# axiom_beta_plugin_module_1xHDMI_v0_8_r1_.net
KiCad netlist of a schematic drawn in EAGLE
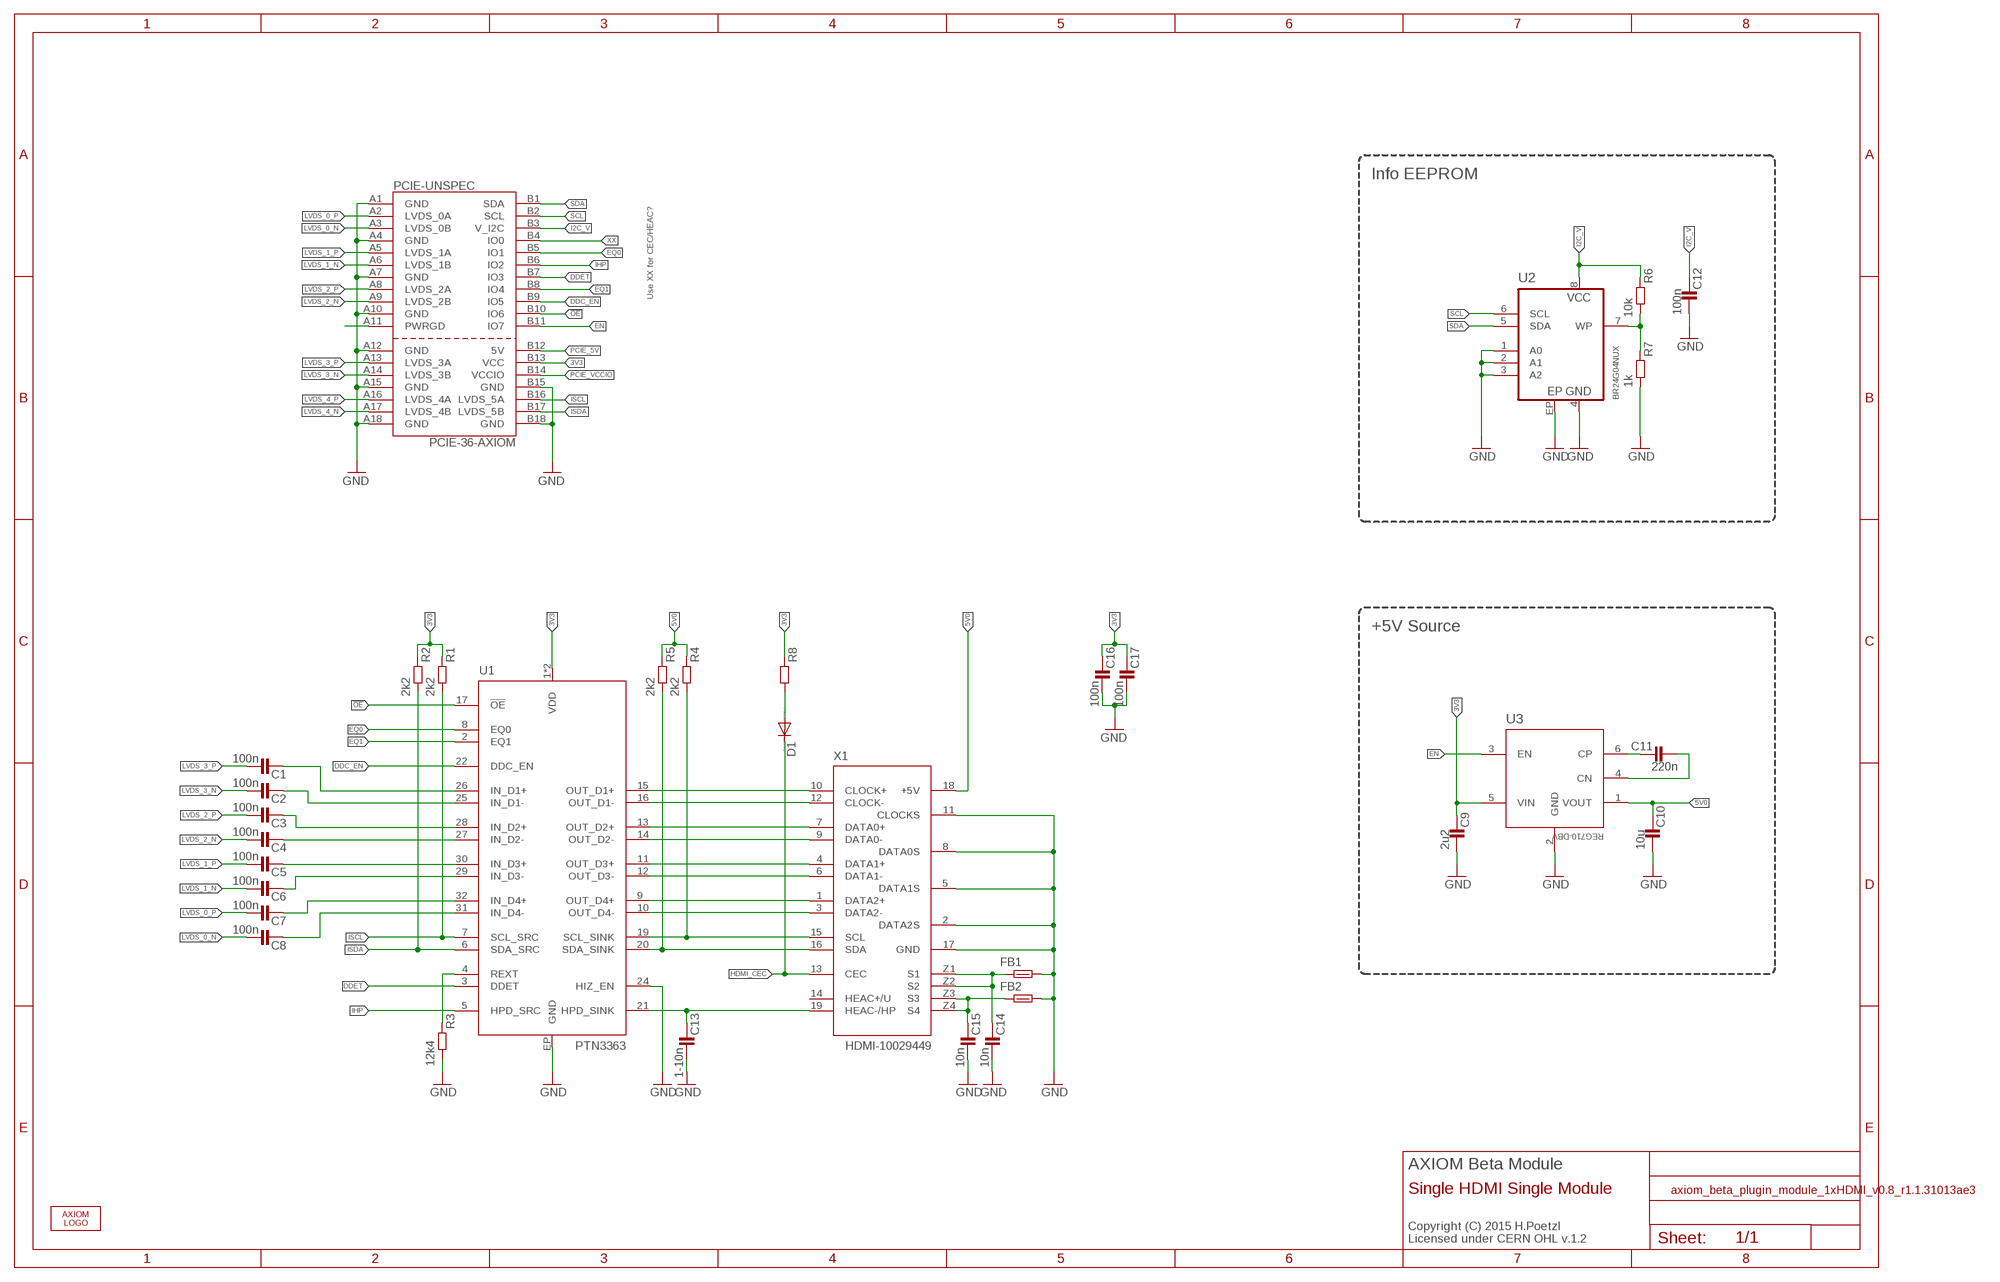
[diagram p0: schematic, sheet 1]

(export (version "E")
  (design (tool "Eeschema 10.0.6"))
  (components
    (comp (ref "C1")
      (value "100n")
      (footprint "eagle-import:0402-C")
      (libsource (lib "eagle-import") (part "C0402-C"))
    )
    (comp (ref "C2")
      (value "100n")
      (footprint "eagle-import:0402-C")
      (libsource (lib "eagle-import") (part "C0402-C"))
    )
    (comp (ref "C3")
      (value "100n")
      (footprint "eagle-import:0402-C")
      (libsource (lib "eagle-import") (part "C0402-C"))
    )
    (comp (ref "C4")
      (value "100n")
      (footprint "eagle-import:0402-C")
      (libsource (lib "eagle-import") (part "C0402-C"))
    )
    (comp (ref "C5")
      (value "100n")
      (footprint "eagle-import:0402-C")
      (libsource (lib "eagle-import") (part "C0402-C"))
    )
    (comp (ref "C6")
      (value "100n")
      (footprint "eagle-import:0402-C")
      (libsource (lib "eagle-import") (part "C0402-C"))
    )
    (comp (ref "C7")
      (value "100n")
      (footprint "eagle-import:0402-C")
      (libsource (lib "eagle-import") (part "C0402-C"))
    )
    (comp (ref "C8")
      (value "100n")
      (footprint "eagle-import:0402-C")
      (libsource (lib "eagle-import") (part "C0402-C"))
    )
    (comp (ref "C9")
      (value "2u2")
      (footprint "eagle-import:0603-B")
      (libsource (lib "eagle-import") (part "C0603-B"))
    )
    (comp (ref "C10")
      (value "10u")
      (footprint "eagle-import:0603-B")
      (libsource (lib "eagle-import") (part "C0603-B"))
    )
    (comp (ref "C11")
      (value "220n")
      (footprint "eagle-import:0603-B")
      (libsource (lib "eagle-import") (part "C0603-B"))
    )
    (comp (ref "C12")
      (value "100n")
      (footprint "eagle-import:0402-B")
      (libsource (lib "eagle-import") (part "C0402-B"))
    )
    (comp (ref "C13")
      (value "1-10n")
      (footprint "eagle-import:0402-B")
      (libsource (lib "eagle-import") (part "C0402-B"))
    )
    (comp (ref "C14")
      (value "10n")
      (footprint "eagle-import:0402-B")
      (libsource (lib "eagle-import") (part "C0402-B"))
    )
    (comp (ref "C15")
      (value "10n")
      (footprint "eagle-import:0402-B")
      (libsource (lib "eagle-import") (part "C0402-B"))
    )
    (comp (ref "C16")
      (value "100n")
      (footprint "eagle-import:0402-B")
      (libsource (lib "eagle-import") (part "C0402-B"))
    )
    (comp (ref "C17")
      (value "100n")
      (footprint "eagle-import:0402-B")
      (libsource (lib "eagle-import") (part "C0402-B"))
    )
    (comp (ref "D1")
      (value "DIODE-SOD523")
      (footprint "eagle-import:SOD523")
      (libsource (lib "eagle-import") (part "DIODE-SOD523"))
    )
    (comp (ref "FB1")
      (value "FB0603-B")
      (footprint "eagle-import:0603-B")
      (libsource (lib "eagle-import") (part "FB0603-B"))
    )
    (comp (ref "FB2")
      (value "FB0603-B")
      (footprint "eagle-import:0603-B")
      (libsource (lib "eagle-import") (part "FB0603-B"))
    )
    (comp (ref "PCIE-UNSPEC")
      (value "PCIE-36-AXIOM")
      (footprint "eagle-import:PCIE-36-AXIOM")
      (libsource (lib "eagle-import") (part "PCIE-36-AXIOM"))
    )
    (comp (ref "R1")
      (value "2k2")
      (footprint "eagle-import:0402-B")
      (libsource (lib "eagle-import") (part "R0402-B"))
    )
    (comp (ref "R2")
      (value "2k2")
      (footprint "eagle-import:0402-B")
      (libsource (lib "eagle-import") (part "R0402-B"))
    )
    (comp (ref "R3")
      (value "12k4")
      (footprint "eagle-import:0402-B")
      (libsource (lib "eagle-import") (part "R0402-B"))
    )
    (comp (ref "R4")
      (value "2k2")
      (footprint "eagle-import:0402-B")
      (libsource (lib "eagle-import") (part "R0402-B"))
    )
    (comp (ref "R5")
      (value "2k2")
      (footprint "eagle-import:0402-B")
      (libsource (lib "eagle-import") (part "R0402-B"))
    )
    (comp (ref "R6")
      (value "10k")
      (footprint "eagle-import:0402-B")
      (libsource (lib "eagle-import") (part "R0402-B"))
    )
    (comp (ref "R7")
      (value "1k")
      (footprint "eagle-import:0402-B")
      (libsource (lib "eagle-import") (part "R0402-B"))
    )
    (comp (ref "R8")
      (value "R0402-B")
      (footprint "eagle-import:0402-B")
      (libsource (lib "eagle-import") (part "R0402-B"))
    )
    (comp (ref "U$1")
      (value "AXIOM_LOGO459X70")
      (footprint "eagle-import:AXIOM_LOGO_459X70")
      (libsource (lib "eagle-import") (part "AXIOM_LOGO459X70"))
    )
    (comp (ref "U1")
      (value "PTN3363")
      (footprint "eagle-import:HVQFN32")
      (libsource (lib "eagle-import") (part "PTN3363"))
    )
    (comp (ref "U2")
      (value "BR24G04NUX")
      (footprint "eagle-import:DFN200X300X100-9N")
      (libsource (lib "eagle-import") (part "BR24G04NUX"))
    )
    (comp (ref "U3")
      (value "REG710-DBV")
      (footprint "eagle-import:DBV")
      (libsource (lib "eagle-import") (part "REG710-DBV"))
    )
    (comp (ref "X1")
      (value "HDMI-10029449")
      (footprint "eagle-import:10029449-X01XLF")
      (libsource (lib "eagle-import") (part "HDMI-10029449"))
    )
  )
  (nets
    (net (code "1") (name "/~{OE}") (class "Default")
      (node (ref "PCIE-UNSPEC") (pin "B10") (pinfunction "IO6_B10") (pintype "passive"))
      (node (ref "U1") (pin "17") (pinfunction "~{OE}_17") (pintype "bidirectional"))
    )
    (net (code "2") (name "3V3") (class "Default")
      (node (ref "C16") (pin "1") (pinfunction "1_1") (pintype "passive"))
      (node (ref "C17") (pin "1") (pinfunction "1_1") (pintype "passive"))
      (node (ref "C9") (pin "1") (pinfunction "1_1") (pintype "passive"))
      (node (ref "PCIE-UNSPEC") (pin "B13") (pinfunction "VCC_B13") (pintype "passive"))
      (node (ref "R1") (pin "1") (pinfunction "1_1") (pintype "passive"))
      (node (ref "R2") (pin "1") (pinfunction "1_1") (pintype "passive"))
      (node (ref "R8") (pin "1") (pinfunction "1_1") (pintype "passive"))
      (node (ref "U1") (pin "1") (pinfunction "VDD_1") (pintype "power_in"))
      (node (ref "U1") (pin "18") (pinfunction "VDD_18") (pintype "power_in"))
      (node (ref "U3") (pin "5") (pinfunction "VIN_5") (pintype "power_in"))
    )
    (net (code "3") (name "5V0") (class "Default")
      (node (ref "C10") (pin "1") (pinfunction "1_1") (pintype "passive"))
      (node (ref "R4") (pin "1") (pinfunction "1_1") (pintype "passive"))
      (node (ref "R5") (pin "1") (pinfunction "1_1") (pintype "passive"))
      (node (ref "U3") (pin "1") (pinfunction "VOUT_1") (pintype "output"))
      (node (ref "X1") (pin "18") (pinfunction "+5V_18") (pintype "power_in"))
    )
    (net (code "4") (name "DDC_EN") (class "Default")
      (node (ref "PCIE-UNSPEC") (pin "B9") (pinfunction "IO5_B9") (pintype "passive"))
      (node (ref "U1") (pin "22") (pinfunction "DDC_EN_22") (pintype "bidirectional"))
    )
    (net (code "5") (name "DDET") (class "Default")
      (node (ref "PCIE-UNSPEC") (pin "B7") (pinfunction "IO3_B7") (pintype "passive"))
      (node (ref "U1") (pin "3") (pinfunction "DDET_3") (pintype "bidirectional"))
    )
    (net (code "6") (name "EN") (class "Default")
      (node (ref "PCIE-UNSPEC") (pin "B11") (pinfunction "IO7_B11") (pintype "passive"))
      (node (ref "U3") (pin "3") (pinfunction "EN_3") (pintype "input"))
    )
    (net (code "7") (name "EQ0") (class "Default")
      (node (ref "PCIE-UNSPEC") (pin "B5") (pinfunction "IO1_B5") (pintype "passive"))
      (node (ref "U1") (pin "8") (pinfunction "EQ0_8") (pintype "bidirectional"))
    )
    (net (code "8") (name "EQ1") (class "Default")
      (node (ref "PCIE-UNSPEC") (pin "B8") (pinfunction "IO4_B8") (pintype "passive"))
      (node (ref "U1") (pin "2") (pinfunction "EQ1_2") (pintype "bidirectional"))
    )
    (net (code "9") (name "GND") (class "Default")
      (node (ref "C10") (pin "2") (pinfunction "2_2") (pintype "passive"))
      (node (ref "C12") (pin "2") (pinfunction "2_2") (pintype "passive"))
      (node (ref "C13") (pin "2") (pinfunction "2_2") (pintype "passive"))
      (node (ref "C14") (pin "2") (pinfunction "2_2") (pintype "passive"))
      (node (ref "C15") (pin "2") (pinfunction "2_2") (pintype "passive"))
      (node (ref "C16") (pin "2") (pinfunction "2_2") (pintype "passive"))
      (node (ref "C17") (pin "2") (pinfunction "2_2") (pintype "passive"))
      (node (ref "C9") (pin "2") (pinfunction "2_2") (pintype "passive"))
      (node (ref "FB1") (pin "2") (pinfunction "2_2") (pintype "passive"))
      (node (ref "FB2") (pin "2") (pinfunction "2_2") (pintype "passive"))
      (node (ref "PCIE-UNSPEC") (pin "A1") (pinfunction "GND_A1") (pintype "passive"))
      (node (ref "PCIE-UNSPEC") (pin "A10") (pinfunction "GND_A10") (pintype "passive"))
      (node (ref "PCIE-UNSPEC") (pin "A12") (pinfunction "GND_A12") (pintype "passive"))
      (node (ref "PCIE-UNSPEC") (pin "A15") (pinfunction "GND_A15") (pintype "passive"))
      (node (ref "PCIE-UNSPEC") (pin "A18") (pinfunction "GND_A18") (pintype "passive"))
      (node (ref "PCIE-UNSPEC") (pin "A4") (pinfunction "GND_A4") (pintype "passive"))
      (node (ref "PCIE-UNSPEC") (pin "A7") (pinfunction "GND_A7") (pintype "passive"))
      (node (ref "PCIE-UNSPEC") (pin "B15") (pinfunction "GND_B15") (pintype "passive"))
      (node (ref "PCIE-UNSPEC") (pin "B18") (pinfunction "GND_B18") (pintype "passive"))
      (node (ref "R3") (pin "2") (pinfunction "2_2") (pintype "passive"))
      (node (ref "R7") (pin "2") (pinfunction "2_2") (pintype "passive"))
      (node (ref "U1") (pin "24") (pinfunction "HIZ_EN_24") (pintype "bidirectional"))
      (node (ref "U1") (pin "EP") (pinfunction "GND_EP") (pintype "bidirectional"))
      (node (ref "U2") (pin "1") (pinfunction "A0_1") (pintype "input"))
      (node (ref "U2") (pin "2") (pinfunction "A1_2") (pintype "input"))
      (node (ref "U2") (pin "3") (pinfunction "A2_3") (pintype "input"))
      (node (ref "U2") (pin "4") (pinfunction "GND_4") (pintype "passive"))
      (node (ref "U2") (pin "EP") (pinfunction "EP_EP") (pintype "passive"))
      (node (ref "U3") (pin "2") (pinfunction "GND_2") (pintype "passive"))
      (node (ref "X1") (pin "11") (pinfunction "CLOCKS_11") (pintype "power_in"))
      (node (ref "X1") (pin "17") (pinfunction "GND_17") (pintype "bidirectional"))
      (node (ref "X1") (pin "2") (pinfunction "DATA2S_2") (pintype "power_in"))
      (node (ref "X1") (pin "5") (pinfunction "DATA1S_5") (pintype "power_in"))
      (node (ref "X1") (pin "8") (pinfunction "DATA0S_8") (pintype "power_in"))
    )
    (net (code "10") (name "HDMI_CEC") (class "Default")
      (node (ref "D1") (pin "C") (pinfunction "C_C") (pintype "passive"))
      (node (ref "X1") (pin "13") (pinfunction "CEC_13") (pintype "bidirectional"))
    )
    (net (code "11") (name "I2C_V") (class "Default")
      (node (ref "C12") (pin "1") (pinfunction "1_1") (pintype "passive"))
      (node (ref "PCIE-UNSPEC") (pin "B3") (pinfunction "V_I2C_B3") (pintype "passive"))
      (node (ref "R6") (pin "1") (pinfunction "1_1") (pintype "passive"))
      (node (ref "U2") (pin "8") (pinfunction "VCC_8") (pintype "power_in"))
    )
    (net (code "12") (name "IHP") (class "Default")
      (node (ref "PCIE-UNSPEC") (pin "B6") (pinfunction "IO2_B6") (pintype "passive"))
      (node (ref "U1") (pin "5") (pinfunction "HPD_SRC_5") (pintype "bidirectional"))
    )
    (net (code "13") (name "ISCL") (class "Default")
      (node (ref "PCIE-UNSPEC") (pin "B16") (pinfunction "LVDS_5A_B16") (pintype "passive"))
      (node (ref "R1") (pin "2") (pinfunction "2_2") (pintype "passive"))
      (node (ref "U1") (pin "7") (pinfunction "SCL_SRC_7") (pintype "bidirectional"))
    )
    (net (code "14") (name "ISDA") (class "Default")
      (node (ref "PCIE-UNSPEC") (pin "B17") (pinfunction "LVDS_5B_B17") (pintype "passive"))
      (node (ref "R2") (pin "2") (pinfunction "2_2") (pintype "passive"))
      (node (ref "U1") (pin "6") (pinfunction "SDA_SRC_6") (pintype "bidirectional"))
    )
    (net (code "15") (name "LVDS_0_N") (class "Default")
      (node (ref "C8") (pin "2") (pinfunction "2_2") (pintype "passive"))
      (node (ref "PCIE-UNSPEC") (pin "A3") (pinfunction "LVDS_0B_A3") (pintype "passive"))
    )
    (net (code "16") (name "LVDS_0_P") (class "Default")
      (node (ref "C7") (pin "2") (pinfunction "2_2") (pintype "passive"))
      (node (ref "PCIE-UNSPEC") (pin "A2") (pinfunction "LVDS_0A_A2") (pintype "passive"))
    )
    (net (code "17") (name "LVDS_1_N") (class "Default")
      (node (ref "C6") (pin "2") (pinfunction "2_2") (pintype "passive"))
      (node (ref "PCIE-UNSPEC") (pin "A6") (pinfunction "LVDS_1B_A6") (pintype "passive"))
    )
    (net (code "18") (name "LVDS_1_P") (class "Default")
      (node (ref "C5") (pin "2") (pinfunction "2_2") (pintype "passive"))
      (node (ref "PCIE-UNSPEC") (pin "A5") (pinfunction "LVDS_1A_A5") (pintype "passive"))
    )
    (net (code "19") (name "LVDS_2_N") (class "Default")
      (node (ref "C4") (pin "2") (pinfunction "2_2") (pintype "passive"))
      (node (ref "PCIE-UNSPEC") (pin "A9") (pinfunction "LVDS_2B_A9") (pintype "passive"))
    )
    (net (code "20") (name "LVDS_2_P") (class "Default")
      (node (ref "C3") (pin "2") (pinfunction "2_2") (pintype "passive"))
      (node (ref "PCIE-UNSPEC") (pin "A8") (pinfunction "LVDS_2A_A8") (pintype "passive"))
    )
    (net (code "21") (name "LVDS_3_N") (class "Default")
      (node (ref "C2") (pin "2") (pinfunction "2_2") (pintype "passive"))
      (node (ref "PCIE-UNSPEC") (pin "A14") (pinfunction "LVDS_3B_A14") (pintype "passive"))
    )
    (net (code "22") (name "LVDS_3_P") (class "Default")
      (node (ref "C1") (pin "2") (pinfunction "2_2") (pintype "passive"))
      (node (ref "PCIE-UNSPEC") (pin "A13") (pinfunction "LVDS_3A_A13") (pintype "passive"))
    )
    (net (code "23") (name "LVDS_4_N") (class "Default")
      (node (ref "PCIE-UNSPEC") (pin "A17") (pinfunction "LVDS_4B_A17") (pintype "passive"))
    )
    (net (code "24") (name "LVDS_4_P") (class "Default")
      (node (ref "PCIE-UNSPEC") (pin "A16") (pinfunction "LVDS_4A_A16") (pintype "passive"))
    )
    (net (code "25") (name "Net-(D1-PadA)") (class "Default")
      (node (ref "D1") (pin "A") (pinfunction "A_A") (pintype "passive"))
      (node (ref "R8") (pin "2") (pinfunction "2_2") (pintype "passive"))
    )
    (net (code "26") (name "Net-(U1-HPD_SINK)") (class "Default")
      (node (ref "C13") (pin "1") (pinfunction "1_1") (pintype "passive"))
      (node (ref "U1") (pin "21") (pinfunction "HPD_SINK_21") (pintype "bidirectional"))
      (node (ref "X1") (pin "19") (pinfunction "HEAC-/HP_19") (pintype "bidirectional"))
    )
    (net (code "27") (name "Net-(U1-IN_D1+)") (class "Default")
      (node (ref "C1") (pin "1") (pinfunction "1_1") (pintype "passive"))
      (node (ref "U1") (pin "26") (pinfunction "IN_D1+_26") (pintype "bidirectional"))
    )
    (net (code "28") (name "Net-(U1-IN_D1-)") (class "Default")
      (node (ref "C2") (pin "1") (pinfunction "1_1") (pintype "passive"))
      (node (ref "U1") (pin "25") (pinfunction "IN_D1-_25") (pintype "bidirectional"))
    )
    (net (code "29") (name "Net-(U1-IN_D2+)") (class "Default")
      (node (ref "C3") (pin "1") (pinfunction "1_1") (pintype "passive"))
      (node (ref "U1") (pin "28") (pinfunction "IN_D2+_28") (pintype "bidirectional"))
    )
    (net (code "30") (name "Net-(U1-IN_D2-)") (class "Default")
      (node (ref "C4") (pin "1") (pinfunction "1_1") (pintype "passive"))
      (node (ref "U1") (pin "27") (pinfunction "IN_D2-_27") (pintype "bidirectional"))
    )
    (net (code "31") (name "Net-(U1-IN_D3+)") (class "Default")
      (node (ref "C5") (pin "1") (pinfunction "1_1") (pintype "passive"))
      (node (ref "U1") (pin "30") (pinfunction "IN_D3+_30") (pintype "bidirectional"))
    )
    (net (code "32") (name "Net-(U1-IN_D3-)") (class "Default")
      (node (ref "C6") (pin "1") (pinfunction "1_1") (pintype "passive"))
      (node (ref "U1") (pin "29") (pinfunction "IN_D3-_29") (pintype "bidirectional"))
    )
    (net (code "33") (name "Net-(U1-IN_D4+)") (class "Default")
      (node (ref "C7") (pin "1") (pinfunction "1_1") (pintype "passive"))
      (node (ref "U1") (pin "32") (pinfunction "IN_D4+_32") (pintype "bidirectional"))
    )
    (net (code "34") (name "Net-(U1-IN_D4-)") (class "Default")
      (node (ref "C8") (pin "1") (pinfunction "1_1") (pintype "passive"))
      (node (ref "U1") (pin "31") (pinfunction "IN_D4-_31") (pintype "bidirectional"))
    )
    (net (code "35") (name "Net-(U1-OUT_D1+)") (class "Default")
      (node (ref "U1") (pin "15") (pinfunction "OUT_D1+_15") (pintype "bidirectional"))
      (node (ref "X1") (pin "10") (pinfunction "CLOCK+_10") (pintype "bidirectional"))
    )
    (net (code "36") (name "Net-(U1-OUT_D1-)") (class "Default")
      (node (ref "U1") (pin "16") (pinfunction "OUT_D1-_16") (pintype "bidirectional"))
      (node (ref "X1") (pin "12") (pinfunction "CLOCK-_12") (pintype "bidirectional"))
    )
    (net (code "37") (name "Net-(U1-OUT_D2+)") (class "Default")
      (node (ref "U1") (pin "13") (pinfunction "OUT_D2+_13") (pintype "bidirectional"))
      (node (ref "X1") (pin "7") (pinfunction "DATA0+_7") (pintype "bidirectional"))
    )
    (net (code "38") (name "Net-(U1-OUT_D2-)") (class "Default")
      (node (ref "U1") (pin "14") (pinfunction "OUT_D2-_14") (pintype "bidirectional"))
      (node (ref "X1") (pin "9") (pinfunction "DATA0-_9") (pintype "bidirectional"))
    )
    (net (code "39") (name "Net-(U1-OUT_D3+)") (class "Default")
      (node (ref "U1") (pin "11") (pinfunction "OUT_D3+_11") (pintype "bidirectional"))
      (node (ref "X1") (pin "4") (pinfunction "DATA1+_4") (pintype "bidirectional"))
    )
    (net (code "40") (name "Net-(U1-OUT_D3-)") (class "Default")
      (node (ref "U1") (pin "12") (pinfunction "OUT_D3-_12") (pintype "bidirectional"))
      (node (ref "X1") (pin "6") (pinfunction "DATA1-_6") (pintype "bidirectional"))
    )
    (net (code "41") (name "Net-(U1-OUT_D4+)") (class "Default")
      (node (ref "U1") (pin "9") (pinfunction "OUT_D4+_9") (pintype "bidirectional"))
      (node (ref "X1") (pin "1") (pinfunction "DATA2+_1") (pintype "bidirectional"))
    )
    (net (code "42") (name "Net-(U1-OUT_D4-)") (class "Default")
      (node (ref "U1") (pin "10") (pinfunction "OUT_D4-_10") (pintype "bidirectional"))
      (node (ref "X1") (pin "3") (pinfunction "DATA2-_3") (pintype "bidirectional"))
    )
    (net (code "43") (name "Net-(U1-REXT)") (class "Default")
      (node (ref "R3") (pin "1") (pinfunction "1_1") (pintype "passive"))
      (node (ref "U1") (pin "4") (pinfunction "REXT_4") (pintype "bidirectional"))
    )
    (net (code "44") (name "Net-(U1-SCL_SINK)") (class "Default")
      (node (ref "R4") (pin "2") (pinfunction "2_2") (pintype "passive"))
      (node (ref "U1") (pin "19") (pinfunction "SCL_SINK_19") (pintype "bidirectional"))
      (node (ref "X1") (pin "15") (pinfunction "SCL_15") (pintype "bidirectional"))
    )
    (net (code "45") (name "Net-(U1-SDA_SINK)") (class "Default")
      (node (ref "R5") (pin "2") (pinfunction "2_2") (pintype "passive"))
      (node (ref "U1") (pin "20") (pinfunction "SDA_SINK_20") (pintype "bidirectional"))
      (node (ref "X1") (pin "16") (pinfunction "SDA_16") (pintype "bidirectional"))
    )
    (net (code "46") (name "Net-(U2-WP)") (class "Default")
      (node (ref "R6") (pin "2") (pinfunction "2_2") (pintype "passive"))
      (node (ref "R7") (pin "1") (pinfunction "1_1") (pintype "passive"))
      (node (ref "U2") (pin "7") (pinfunction "WP_7") (pintype "input"))
    )
    (net (code "47") (name "Net-(U3-CN)") (class "Default")
      (node (ref "C11") (pin "2") (pinfunction "2_2") (pintype "passive"))
      (node (ref "U3") (pin "4") (pinfunction "CN_4") (pintype "power_in"))
    )
    (net (code "48") (name "Net-(U3-CP)") (class "Default")
      (node (ref "C11") (pin "1") (pinfunction "1_1") (pintype "passive"))
      (node (ref "U3") (pin "6") (pinfunction "CP_6") (pintype "output"))
    )
    (net (code "49") (name "Net-(X1-S1)") (class "Default")
      (node (ref "C14") (pin "1") (pinfunction "1_1") (pintype "passive"))
      (node (ref "FB1") (pin "1") (pinfunction "1_1") (pintype "passive"))
      (node (ref "X1") (pin "Z1") (pinfunction "S1_Z1") (pintype "power_in"))
      (node (ref "X1") (pin "Z2") (pinfunction "S2_Z2") (pintype "power_in"))
    )
    (net (code "50") (name "Net-(X1-S3)") (class "Default")
      (node (ref "C15") (pin "1") (pinfunction "1_1") (pintype "passive"))
      (node (ref "FB2") (pin "1") (pinfunction "1_1") (pintype "passive"))
      (node (ref "X1") (pin "Z3") (pinfunction "S3_Z3") (pintype "power_in"))
      (node (ref "X1") (pin "Z4") (pinfunction "S4_Z4") (pintype "power_in"))
    )
    (net (code "51") (name "PCIE_5V") (class "Default")
      (node (ref "PCIE-UNSPEC") (pin "B12") (pinfunction "5V_B12") (pintype "passive"))
    )
    (net (code "52") (name "PCIE_VCCIO") (class "Default")
      (node (ref "PCIE-UNSPEC") (pin "B14") (pinfunction "VCCIO_B14") (pintype "passive"))
    )
    (net (code "53") (name "SCL") (class "Default")
      (node (ref "PCIE-UNSPEC") (pin "B2") (pinfunction "SCL_B2") (pintype "passive"))
      (node (ref "U2") (pin "6") (pinfunction "SCL_6") (pintype "input"))
    )
    (net (code "54") (name "SDA") (class "Default")
      (node (ref "PCIE-UNSPEC") (pin "B1") (pinfunction "SDA_B1") (pintype "passive"))
      (node (ref "U2") (pin "5") (pinfunction "SDA_5") (pintype "bidirectional"))
    )
    (net (code "55") (name "XX") (class "Default")
      (node (ref "PCIE-UNSPEC") (pin "B4") (pinfunction "IO0_B4") (pintype "passive"))
    )
    (net (code "56") (name "unconnected-(PCIE-UNSPEC-PWRGD-PadA11)") (class "Default")
      (node (ref "PCIE-UNSPEC") (pin "A11") (pinfunction "PWRGD_A11") (pintype "passive"))
    )
    (net (code "57") (name "unconnected-(X1-HEAC+{slash}U-Pad14)") (class "Default")
      (node (ref "X1") (pin "14") (pinfunction "HEAC+/U_14") (pintype "bidirectional"))
    )
  )
)
